# PowerDistBoard.net
KiCad netlist of a schematic drawn in EAGLE
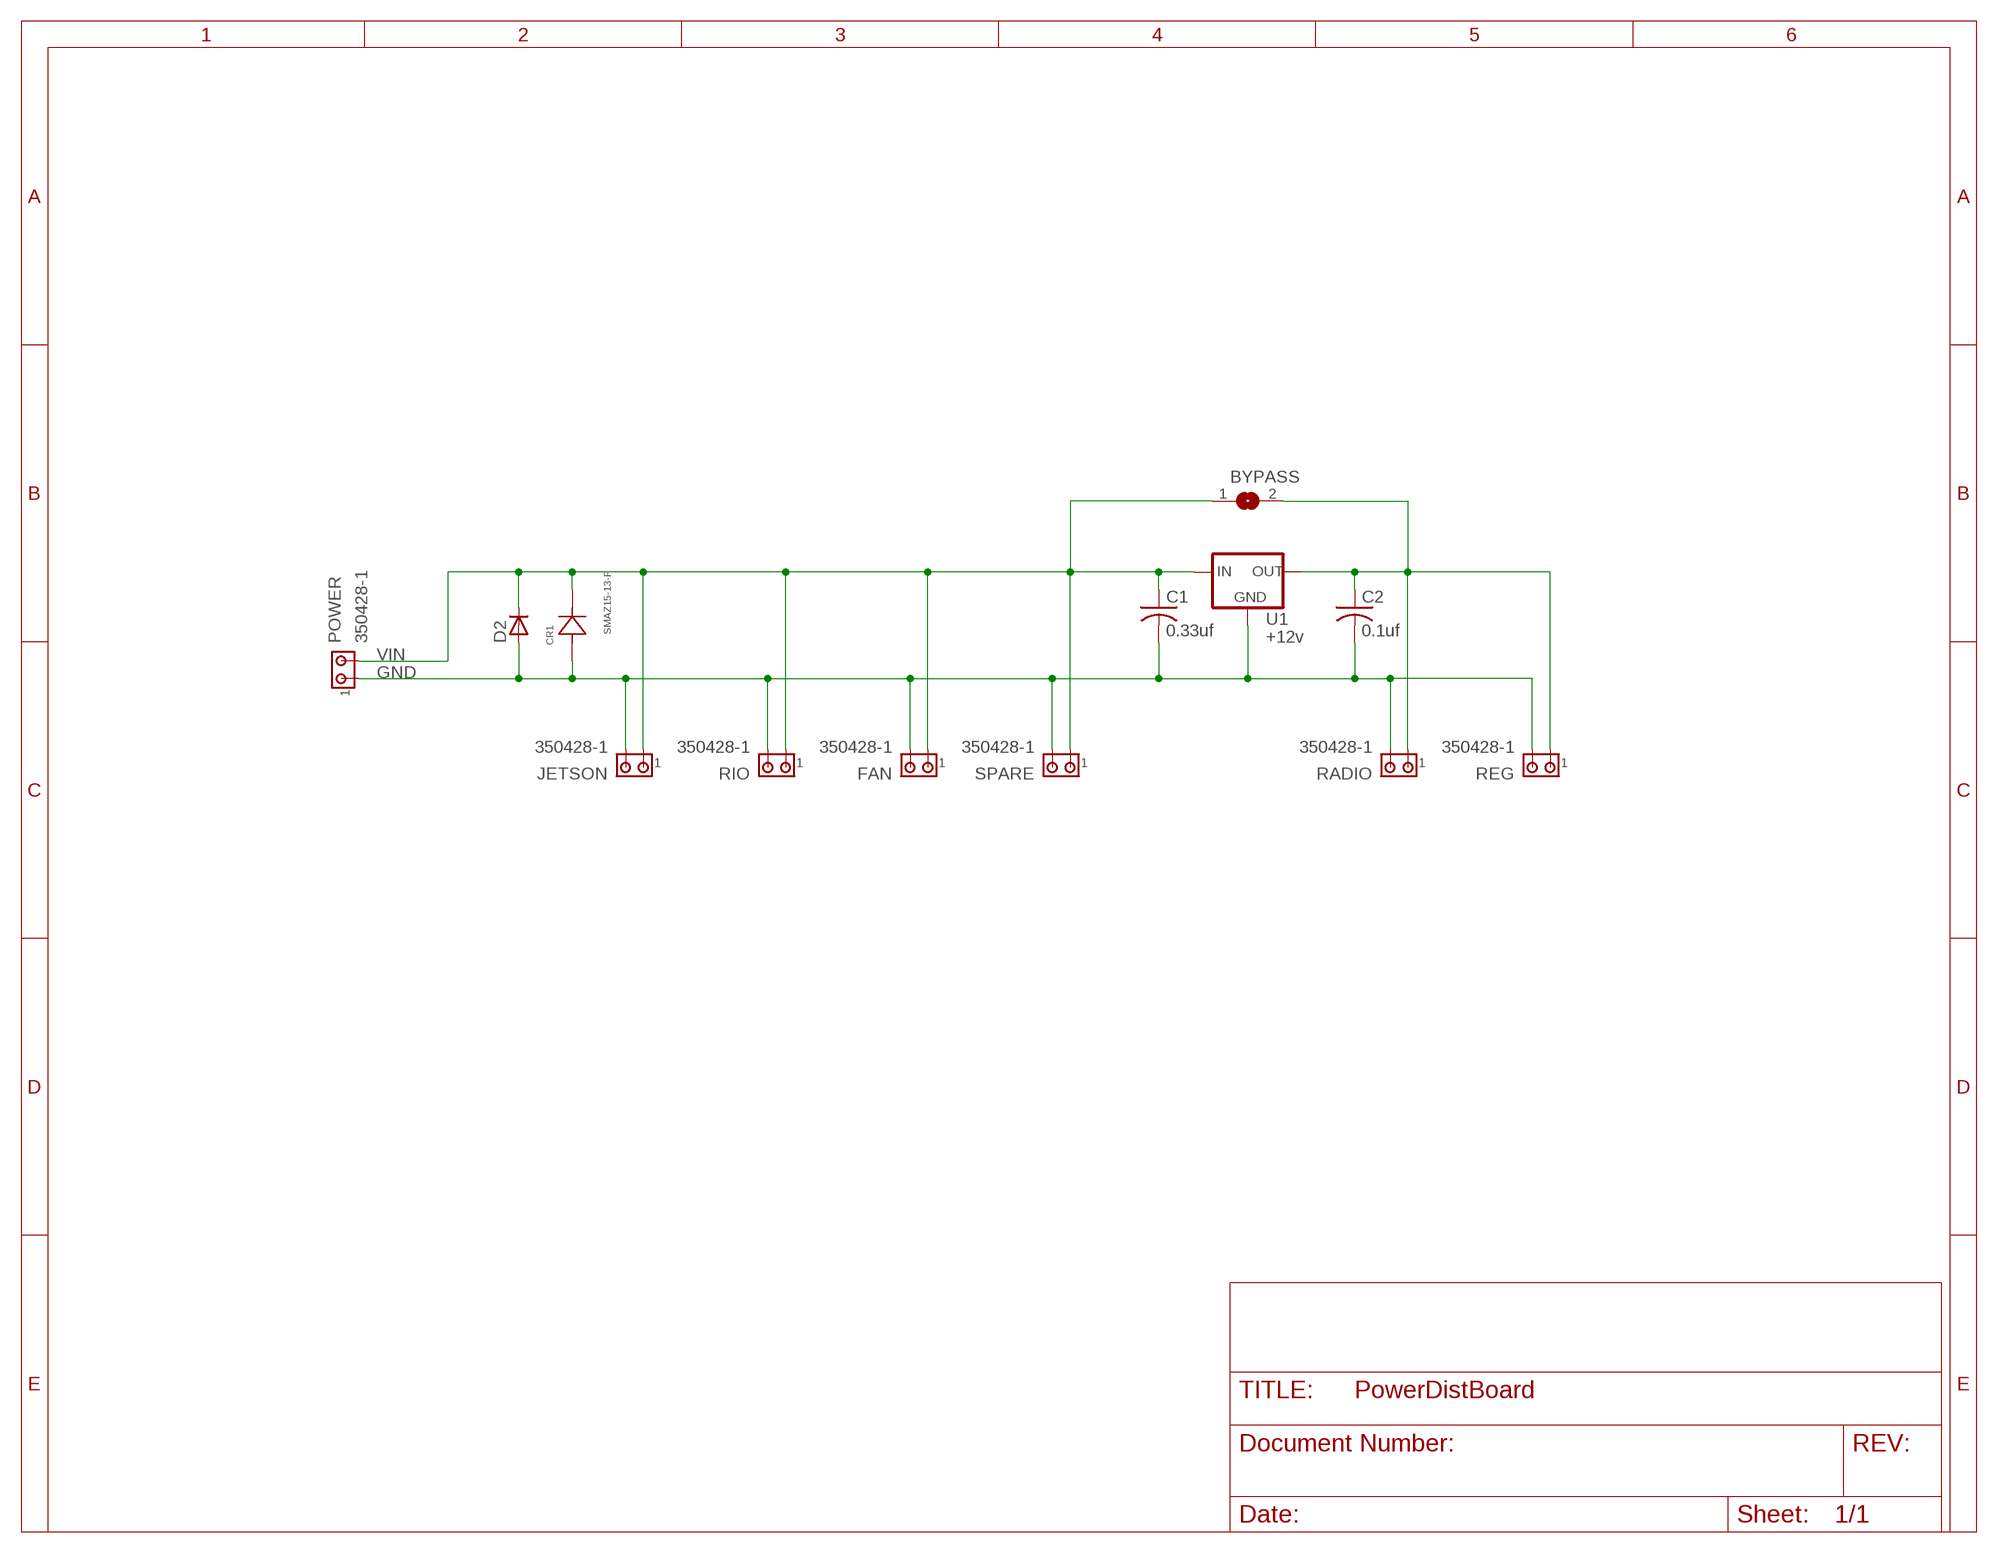
[diagram p0: schematic, sheet 1]

(export (version "E")
  (design (tool "Eeschema 10.0.6"))
  (components
    (comp (ref "BYPASS")
      (value "SJW")
      (footprint "eagle-import:SJW")
      (libsource (lib "eagle-import") (part "SJW"))
    )
    (comp (ref "C1")
      (value "0.33uf")
      (footprint "eagle-import:C0603")
      (libsource (lib "eagle-import") (part "C-USC0603"))
    )
    (comp (ref "C2")
      (value "0.1uf")
      (footprint "eagle-import:C0603")
      (libsource (lib "eagle-import") (part "C-USC0603"))
    )
    (comp (ref "CR1")
      (value "SMAZ15-13-F")
      (footprint "eagle-import:SMA")
      (fields (field (name "MANUFACTURER_PART_NUMBER") "SMAZ1513F"))
      (libsource (lib "eagle-import") (part "SMAZ15-13-F"))
    )
    (comp (ref "D2")
      (value "D-SOD-80")
      (footprint "eagle-import:SOD80")
      (libsource (lib "eagle-import") (part "D-SOD-80"))
    )
    (comp (ref "FAN")
      (value "350428-1")
      (footprint "eagle-import:350428-1")
      (libsource (lib "eagle-import") (part "350428-1"))
    )
    (comp (ref "JETSON")
      (value "350428-1")
      (footprint "eagle-import:350428-1")
      (libsource (lib "eagle-import") (part "350428-1"))
    )
    (comp (ref "POWER")
      (value "350428-1")
      (footprint "eagle-import:350428-1")
      (libsource (lib "eagle-import") (part "350428-1"))
    )
    (comp (ref "RADIO")
      (value "350428-1")
      (footprint "eagle-import:350428-1")
      (libsource (lib "eagle-import") (part "350428-1"))
    )
    (comp (ref "REG")
      (value "350428-1")
      (footprint "eagle-import:350428-1")
      (libsource (lib "eagle-import") (part "350428-1"))
    )
    (comp (ref "RIO")
      (value "350428-1")
      (footprint "eagle-import:350428-1")
      (libsource (lib "eagle-import") (part "350428-1"))
    )
    (comp (ref "SPARE")
      (value "350428-1")
      (footprint "eagle-import:350428-1")
      (libsource (lib "eagle-import") (part "350428-1"))
    )
    (comp (ref "U1")
      (value "+12v")
      (footprint "eagle-import:TO-252")
      (libsource (lib "eagle-import") (part "V_REG_78XX7812"))
    )
  )
  (nets
    (net (code "1") (name "/GND") (class "Default")
      (node (ref "C1") (pin "2") (pinfunction "2_2") (pintype "passive"))
      (node (ref "C2") (pin "2") (pinfunction "2_2") (pintype "passive"))
      (node (ref "CR1") (pin "2") (pinfunction "21_2") (pintype "passive"))
      (node (ref "D2") (pin "2") (pinfunction "A_2") (pintype "passive"))
      (node (ref "FAN") (pin "2") (pinfunction "2_2") (pintype "passive"))
      (node (ref "JETSON") (pin "2") (pinfunction "2_2") (pintype "passive"))
      (node (ref "POWER") (pin "1") (pinfunction "1_1") (pintype "passive"))
      (node (ref "RADIO") (pin "2") (pinfunction "2_2") (pintype "passive"))
      (node (ref "REG") (pin "2") (pinfunction "2_2") (pintype "passive"))
      (node (ref "RIO") (pin "2") (pinfunction "2_2") (pintype "passive"))
      (node (ref "SPARE") (pin "2") (pinfunction "2_2") (pintype "passive"))
      (node (ref "U1") (pin "3") (pinfunction "GND_3") (pintype "input"))
    )
    (net (code "2") (name "/VIN") (class "Default")
      (node (ref "BYPASS") (pin "1") (pinfunction "1_1") (pintype "passive"))
      (node (ref "C1") (pin "1") (pinfunction "1_1") (pintype "passive"))
      (node (ref "CR1") (pin "1") (pinfunction "12_1") (pintype "passive"))
      (node (ref "D2") (pin "1") (pinfunction "C_1") (pintype "passive"))
      (node (ref "FAN") (pin "1") (pinfunction "1_1") (pintype "passive"))
      (node (ref "JETSON") (pin "1") (pinfunction "1_1") (pintype "passive"))
      (node (ref "POWER") (pin "2") (pinfunction "2_2") (pintype "passive"))
      (node (ref "RIO") (pin "1") (pinfunction "1_1") (pintype "passive"))
      (node (ref "SPARE") (pin "1") (pinfunction "1_1") (pintype "passive"))
      (node (ref "U1") (pin "1") (pinfunction "IN_1") (pintype "input"))
    )
    (net (code "3") (name "Net-(U1-OUT)") (class "Default")
      (node (ref "BYPASS") (pin "2") (pinfunction "2_2") (pintype "passive"))
      (node (ref "C2") (pin "1") (pinfunction "1_1") (pintype "passive"))
      (node (ref "RADIO") (pin "1") (pinfunction "1_1") (pintype "passive"))
      (node (ref "REG") (pin "1") (pinfunction "1_1") (pintype "passive"))
      (node (ref "U1") (pin "2") (pinfunction "OUT_2") (pintype "passive"))
    )
  )
)
